# Controller.net
KiCad netlist of a schematic drawn in Altium Designer
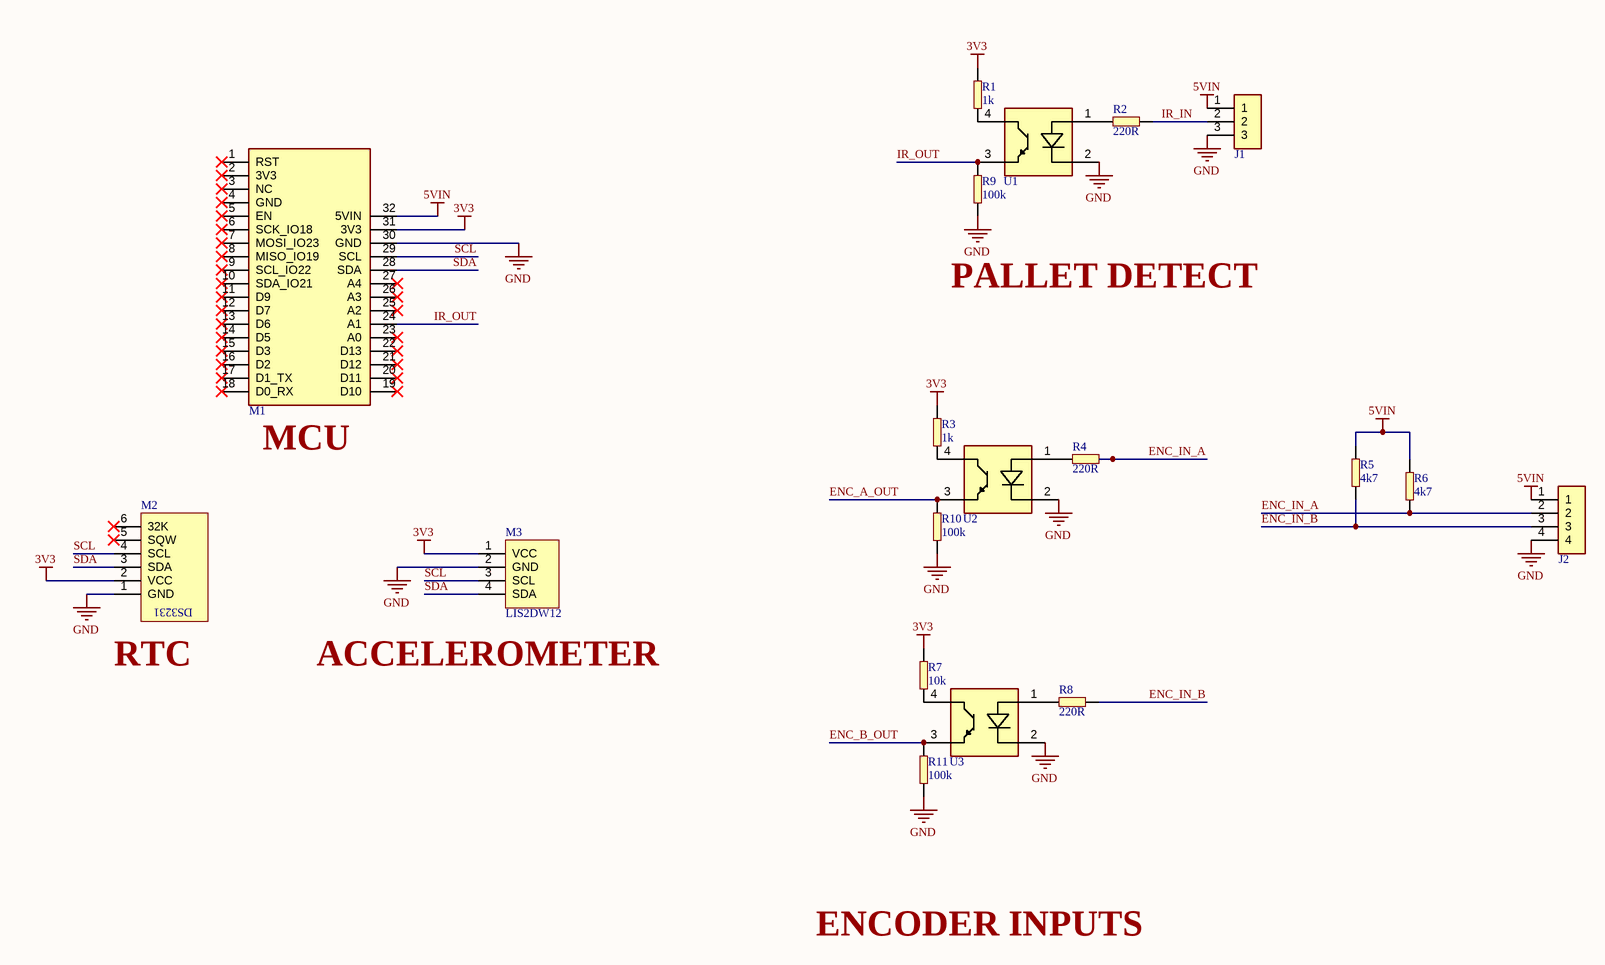
[diagram p0: Controller.SchDoc]

(export (version "E")
  (design (tool "Eeschema 10.0.6"))
  (components
    (comp (ref "J1")
      (value "Terminal_Block_3Pin_2.54P")
      (footprint "Terminal_Block_3Pin_2.54P")
      (description "TERMINAL BLOCK 3 PIN 2.54 PITCH")
      (libsource (lib "Connectors") (part "Terminal_Block_3Pin_2.54P"))
    )
    (comp (ref "J2")
      (value "Terminal_Block_4Pin_2.54P")
      (footprint "Terminal_Block_4Pin_2.54P")
      (description "TERMINAL BLOCK 4 PIN 2.54 PITCH")
      (libsource (lib "Connectors") (part "Terminal_Block_4Pin_2.54P"))
    )
    (comp (ref "M1")
      (value "FireBeetle_32E")
      (footprint "DFR0654")
      (description "FIREBEETLE ESP32-E IOT MICROCONT")
      (fields (field (name "MANUFACTURER") "DFRobot"))
      (libsource (lib "ESPModule") (part "FireBeetle_32E"))
    )
    (comp (ref "M2")
      (value "DS3231_HW-084")
      (footprint "DS3231_HW-084")
      (description "DS3231 Time Module , HW-084")
      (libsource (lib "Time") (part "DS3231_HW-084"))
    )
    (comp (ref "M3")
      (value "LIS2DW12")
      (footprint "SEN0409")
      (description "GRAVITY LIS2DW12 ACCELEROMETER")
      (fields (field (name "Comment") "SEN0409"))
      (libsource (lib "WiredModule") (part "SEN0409"))
    )
    (comp (ref "R1")
      (value "1k")
      (footprint "RES_0603")
      (description "RES_0603")
      (fields (field (name "Comment") "ERP_101-1"))
      (libsource (lib "Resistor") (part "RES_0603"))
    )
    (comp (ref "R2")
      (value "220R")
      (footprint "RES_0603")
      (description "RES_0603")
      (fields (field (name "Comment") "ERP_101-1"))
      (libsource (lib "") (part "RES_0603_1"))
    )
    (comp (ref "R3")
      (value "1k")
      (footprint "RES_0603")
      (description "RES_0603")
      (fields (field (name "Comment") "ERP_101-1"))
      (libsource (lib "Resistor") (part "RES_0603"))
    )
    (comp (ref "R4")
      (value "220R")
      (footprint "RES_0603")
      (description "RES_0603")
      (fields (field (name "Comment") "ERP_101-1"))
      (libsource (lib "") (part "RES_0603_1"))
    )
    (comp (ref "R5")
      (value "4k7")
      (footprint "RES_0603")
      (description "RES_0603")
      (fields (field (name "Comment") "ERP_101-1"))
      (libsource (lib "Resistor") (part "RES_0603"))
    )
    (comp (ref "R6")
      (value "4k7")
      (footprint "RES_0603")
      (description "RES_0603")
      (fields (field (name "Comment") "ERP_101-1"))
      (libsource (lib "Resistor") (part "RES_0603"))
    )
    (comp (ref "R7")
      (value "10k")
      (footprint "RES_0603")
      (description "RES_0603")
      (fields (field (name "Comment") "ERP_101-1"))
      (libsource (lib "Resistor") (part "RES_0603"))
    )
    (comp (ref "R8")
      (value "220R")
      (footprint "RES_0603")
      (description "RES_0603")
      (fields (field (name "Comment") "ERP_101-1"))
      (libsource (lib "") (part "RES_0603_1"))
    )
    (comp (ref "R9")
      (value "100k")
      (footprint "RES_0603")
      (description "RES_0603")
      (fields (field (name "Comment") "ERP_101-1"))
      (libsource (lib "Resistor") (part "RES_0603"))
    )
    (comp (ref "R10")
      (value "100k")
      (footprint "RES_0603")
      (description "RES_0603")
      (fields (field (name "Comment") "ERP_101-1"))
      (libsource (lib "Resistor") (part "RES_0603"))
    )
    (comp (ref "R11")
      (value "100k")
      (footprint "RES_0603")
      (description "RES_0603")
      (fields (field (name "Comment") "ERP_101-1"))
      (libsource (lib "Resistor") (part "RES_0603"))
    )
    (comp (ref "U1")
      (value "PC817_DIP")
      (footprint "PC817_DIP")
      (description "DIP-4 Transistor Output Optocoupler")
      (libsource (lib "Optocoupler") (part "PC817_DIP"))
    )
    (comp (ref "U2")
      (value "PC817_DIP")
      (footprint "PC817_DIP")
      (description "DIP-4 Transistor Output Optocoupler")
      (libsource (lib "Optocoupler") (part "PC817_DIP"))
    )
    (comp (ref "U3")
      (value "PC817_DIP")
      (footprint "PC817_DIP")
      (description "DIP-4 Transistor Output Optocoupler")
      (libsource (lib "Optocoupler") (part "PC817_DIP"))
    )
  )
  (nets
    (net (code "1") (name "/ENC_A_OUT") (class "Default")
      (node (ref "R10") (pin "2") (pinfunction "2_2") (pintype "passive"))
      (node (ref "U2") (pin "3") (pinfunction "EMITTER_3") (pintype "passive"))
    )
    (net (code "2") (name "/ENC_B_OUT") (class "Default")
      (node (ref "R11") (pin "2") (pinfunction "2_2") (pintype "passive"))
      (node (ref "U3") (pin "3") (pinfunction "EMITTER_3") (pintype "passive"))
    )
    (net (code "3") (name "/ENC_IN_A") (class "Default")
      (node (ref "J2") (pin "2") (pinfunction "2_2") (pintype "passive"))
      (node (ref "R4") (pin "2") (pinfunction "2_2") (pintype "passive"))
      (node (ref "R6") (pin "1") (pinfunction "1_1") (pintype "passive"))
    )
    (net (code "4") (name "/ENC_IN_B") (class "Default")
      (node (ref "J2") (pin "3") (pinfunction "3_3") (pintype "passive"))
      (node (ref "R5") (pin "1") (pinfunction "1_1") (pintype "passive"))
      (node (ref "R8") (pin "2") (pinfunction "2_2") (pintype "passive"))
    )
    (net (code "5") (name "/IR_IN") (class "Default")
      (node (ref "J1") (pin "2") (pinfunction "2_2") (pintype "passive"))
      (node (ref "R2") (pin "2") (pinfunction "2_2") (pintype "passive"))
    )
    (net (code "6") (name "/IR_OUT") (class "Default")
      (node (ref "M1") (pin "24") (pinfunction "A1_24") (pintype "passive"))
      (node (ref "R9") (pin "2") (pinfunction "2_2") (pintype "passive"))
      (node (ref "U1") (pin "3") (pinfunction "EMITTER_3") (pintype "passive"))
    )
    (net (code "7") (name "/SCL") (class "Default")
      (node (ref "M1") (pin "29") (pinfunction "SCL_29") (pintype "passive"))
      (node (ref "M2") (pin "4") (pinfunction "SCL_4") (pintype "passive"))
      (node (ref "M3") (pin "3") (pinfunction "SCL_3") (pintype "passive"))
    )
    (net (code "8") (name "/SDA") (class "Default")
      (node (ref "M1") (pin "28") (pinfunction "SDA_28") (pintype "passive"))
      (node (ref "M2") (pin "3") (pinfunction "SDA_3") (pintype "passive"))
      (node (ref "M3") (pin "4") (pinfunction "SDA_4") (pintype "passive"))
    )
    (net (code "9") (name "3V3") (class "Default")
      (node (ref "M1") (pin "31") (pinfunction "3V3_31") (pintype "passive"))
      (node (ref "M2") (pin "2") (pinfunction "VCC_2") (pintype "passive"))
      (node (ref "M3") (pin "1") (pinfunction "VCC_1") (pintype "passive"))
      (node (ref "R1") (pin "2") (pinfunction "2_2") (pintype "passive"))
      (node (ref "R3") (pin "2") (pinfunction "2_2") (pintype "passive"))
      (node (ref "R7") (pin "2") (pinfunction "2_2") (pintype "passive"))
    )
    (net (code "10") (name "5VIN") (class "Default")
      (node (ref "J1") (pin "1") (pinfunction "1_1") (pintype "passive"))
      (node (ref "J2") (pin "1") (pinfunction "1_1") (pintype "passive"))
      (node (ref "M1") (pin "32") (pinfunction "5VIN_32") (pintype "passive"))
      (node (ref "R5") (pin "2") (pinfunction "2_2") (pintype "passive"))
      (node (ref "R6") (pin "2") (pinfunction "2_2") (pintype "passive"))
    )
    (net (code "11") (name "GND") (class "Default")
      (node (ref "J1") (pin "3") (pinfunction "3_3") (pintype "passive"))
      (node (ref "J2") (pin "4") (pinfunction "4_4") (pintype "passive"))
      (node (ref "M1") (pin "30") (pinfunction "GND_30") (pintype "passive"))
      (node (ref "M2") (pin "1") (pinfunction "GND_1") (pintype "passive"))
      (node (ref "M3") (pin "2") (pinfunction "GND_2") (pintype "passive"))
      (node (ref "R10") (pin "1") (pinfunction "1_1") (pintype "passive"))
      (node (ref "R11") (pin "1") (pinfunction "1_1") (pintype "passive"))
      (node (ref "R9") (pin "1") (pinfunction "1_1") (pintype "passive"))
      (node (ref "U1") (pin "2") (pinfunction "CATHODE_2") (pintype "passive"))
      (node (ref "U2") (pin "2") (pinfunction "CATHODE_2") (pintype "passive"))
      (node (ref "U3") (pin "2") (pinfunction "CATHODE_2") (pintype "passive"))
    )
    (net (code "12") (name "Net-(U1-ANODE)") (class "Default")
      (node (ref "R2") (pin "1") (pinfunction "1_1") (pintype "passive"))
      (node (ref "U1") (pin "1") (pinfunction "ANODE_1") (pintype "passive"))
    )
    (net (code "13") (name "Net-(U1-COLLECTOR)") (class "Default")
      (node (ref "R1") (pin "1") (pinfunction "1_1") (pintype "passive"))
      (node (ref "U1") (pin "4") (pinfunction "COLLECTOR_4") (pintype "passive"))
    )
    (net (code "14") (name "Net-(U2-ANODE)") (class "Default")
      (node (ref "R4") (pin "1") (pinfunction "1_1") (pintype "passive"))
      (node (ref "U2") (pin "1") (pinfunction "ANODE_1") (pintype "passive"))
    )
    (net (code "15") (name "Net-(U2-COLLECTOR)") (class "Default")
      (node (ref "R3") (pin "1") (pinfunction "1_1") (pintype "passive"))
      (node (ref "U2") (pin "4") (pinfunction "COLLECTOR_4") (pintype "passive"))
    )
    (net (code "16") (name "Net-(U3-ANODE)") (class "Default")
      (node (ref "R8") (pin "1") (pinfunction "1_1") (pintype "passive"))
      (node (ref "U3") (pin "1") (pinfunction "ANODE_1") (pintype "passive"))
    )
    (net (code "17") (name "Net-(U3-COLLECTOR)") (class "Default")
      (node (ref "R7") (pin "1") (pinfunction "1_1") (pintype "passive"))
      (node (ref "U3") (pin "4") (pinfunction "COLLECTOR_4") (pintype "passive"))
    )
    (net (code "18") (name "unconnected-(M1-3V3-Pad2)") (class "Default")
      (node (ref "M1") (pin "2") (pinfunction "3V3_2") (pintype "passive+no_connect"))
    )
    (net (code "19") (name "unconnected-(M1-A0-Pad23)") (class "Default")
      (node (ref "M1") (pin "23") (pinfunction "A0_23") (pintype "passive+no_connect"))
    )
    (net (code "20") (name "unconnected-(M1-A2-Pad25)") (class "Default")
      (node (ref "M1") (pin "25") (pinfunction "A2_25") (pintype "passive+no_connect"))
    )
    (net (code "21") (name "unconnected-(M1-A3-Pad26)") (class "Default")
      (node (ref "M1") (pin "26") (pinfunction "A3_26") (pintype "passive+no_connect"))
    )
    (net (code "22") (name "unconnected-(M1-A4-Pad27)") (class "Default")
      (node (ref "M1") (pin "27") (pinfunction "A4_27") (pintype "passive+no_connect"))
    )
    (net (code "23") (name "unconnected-(M1-D0_RX-Pad18)") (class "Default")
      (node (ref "M1") (pin "18") (pinfunction "D0_RX_18") (pintype "passive+no_connect"))
    )
    (net (code "24") (name "unconnected-(M1-D1_TX-Pad17)") (class "Default")
      (node (ref "M1") (pin "17") (pinfunction "D1_TX_17") (pintype "passive+no_connect"))
    )
    (net (code "25") (name "unconnected-(M1-D2-Pad16)") (class "Default")
      (node (ref "M1") (pin "16") (pinfunction "D2_16") (pintype "passive+no_connect"))
    )
    (net (code "26") (name "unconnected-(M1-D3-Pad15)") (class "Default")
      (node (ref "M1") (pin "15") (pinfunction "D3_15") (pintype "passive+no_connect"))
    )
    (net (code "27") (name "unconnected-(M1-D5-Pad14)") (class "Default")
      (node (ref "M1") (pin "14") (pinfunction "D5_14") (pintype "passive+no_connect"))
    )
    (net (code "28") (name "unconnected-(M1-D6-Pad13)") (class "Default")
      (node (ref "M1") (pin "13") (pinfunction "D6_13") (pintype "passive+no_connect"))
    )
    (net (code "29") (name "unconnected-(M1-D7-Pad12)") (class "Default")
      (node (ref "M1") (pin "12") (pinfunction "D7_12") (pintype "passive+no_connect"))
    )
    (net (code "30") (name "unconnected-(M1-D9-Pad11)") (class "Default")
      (node (ref "M1") (pin "11") (pinfunction "D9_11") (pintype "passive+no_connect"))
    )
    (net (code "31") (name "unconnected-(M1-D10-Pad19)") (class "Default")
      (node (ref "M1") (pin "19") (pinfunction "D10_19") (pintype "passive+no_connect"))
    )
    (net (code "32") (name "unconnected-(M1-D11-Pad20)") (class "Default")
      (node (ref "M1") (pin "20") (pinfunction "D11_20") (pintype "passive+no_connect"))
    )
    (net (code "33") (name "unconnected-(M1-D12-Pad21)") (class "Default")
      (node (ref "M1") (pin "21") (pinfunction "D12_21") (pintype "passive+no_connect"))
    )
    (net (code "34") (name "unconnected-(M1-D13-Pad22)") (class "Default")
      (node (ref "M1") (pin "22") (pinfunction "D13_22") (pintype "passive+no_connect"))
    )
    (net (code "35") (name "unconnected-(M1-EN-Pad5)") (class "Default")
      (node (ref "M1") (pin "5") (pinfunction "EN_5") (pintype "passive+no_connect"))
    )
    (net (code "36") (name "unconnected-(M1-GND-Pad4)") (class "Default")
      (node (ref "M1") (pin "4") (pinfunction "GND_4") (pintype "passive+no_connect"))
    )
    (net (code "37") (name "unconnected-(M1-MISO_IO19-Pad8)") (class "Default")
      (node (ref "M1") (pin "8") (pinfunction "MISO_IO19_8") (pintype "passive+no_connect"))
    )
    (net (code "38") (name "unconnected-(M1-MOSI_IO23-Pad7)") (class "Default")
      (node (ref "M1") (pin "7") (pinfunction "MOSI_IO23_7") (pintype "passive+no_connect"))
    )
    (net (code "39") (name "unconnected-(M1-NC-Pad3)") (class "Default")
      (node (ref "M1") (pin "3") (pinfunction "NC_3") (pintype "passive+no_connect"))
    )
    (net (code "40") (name "unconnected-(M1-RST-Pad1)") (class "Default")
      (node (ref "M1") (pin "1") (pinfunction "RST_1") (pintype "passive+no_connect"))
    )
    (net (code "41") (name "unconnected-(M1-SCK_IO18-Pad6)") (class "Default")
      (node (ref "M1") (pin "6") (pinfunction "SCK_IO18_6") (pintype "passive+no_connect"))
    )
    (net (code "42") (name "unconnected-(M1-SCL_IO22-Pad9)") (class "Default")
      (node (ref "M1") (pin "9") (pinfunction "SCL_IO22_9") (pintype "passive+no_connect"))
    )
    (net (code "43") (name "unconnected-(M1-SDA_IO21-Pad10)") (class "Default")
      (node (ref "M1") (pin "10") (pinfunction "SDA_IO21_10") (pintype "passive+no_connect"))
    )
    (net (code "44") (name "unconnected-(M2-32K-Pad6)") (class "Default")
      (node (ref "M2") (pin "6") (pinfunction "32K_6") (pintype "passive+no_connect"))
    )
    (net (code "45") (name "unconnected-(M2-SQW-Pad5)") (class "Default")
      (node (ref "M2") (pin "5") (pinfunction "SQW_5") (pintype "passive+no_connect"))
    )
  )
)
